# GBWandR1.net
KiCad netlist of a schematic drawn in EAGLE
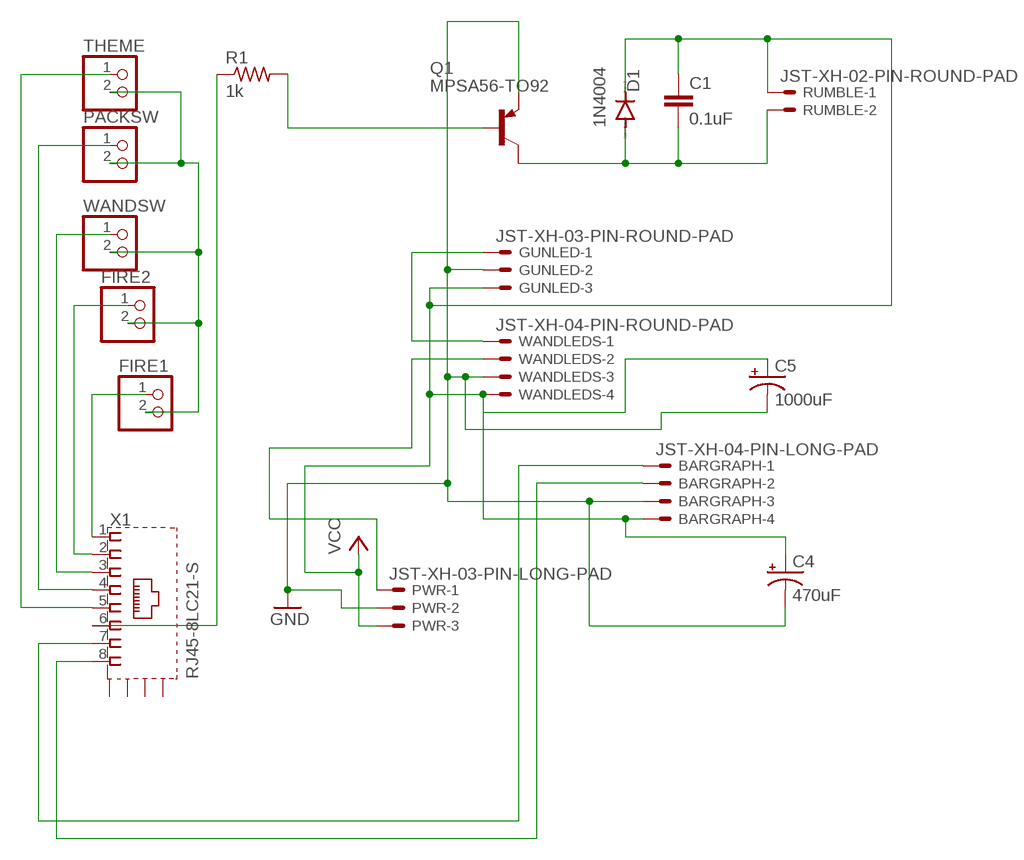
[diagram p0: schematic, sheet 1]

(export (version "E")
  (design (tool "Eeschema 10.0.6"))
  (components
    (comp (ref "BARGRAPH")
      (value "JST-XH-04-PIN-LONG-PAD")
      (footprint "eagle-import:JST-XH-04-PACKAGE-LONG-PAD")
      (libsource (lib "eagle-import") (part "JST-XH-04-PIN-LONG-PAD"))
    )
    (comp (ref "C1")
      (value "0.1uF")
      (footprint "eagle-import:C050-024X044")
      (libsource (lib "eagle-import") (part "C-EU050-024X044"))
    )
    (comp (ref "C4")
      (value "470uF")
      (footprint "eagle-import:E3,5-8")
      (libsource (lib "eagle-import") (part "CPOL-USE3.5-8"))
    )
    (comp (ref "C5")
      (value "1000uF")
      (footprint "eagle-import:E3,5-8")
      (libsource (lib "eagle-import") (part "CPOL-USE3.5-8"))
    )
    (comp (ref "D1")
      (value "1N4004")
      (footprint "eagle-import:DO41-10")
      (libsource (lib "eagle-import") (part "1N4004"))
    )
    (comp (ref "FIRE1")
      (value "PINHD-1X2")
      (footprint "eagle-import:1X02")
      (libsource (lib "eagle-import") (part "PINHD-1X2"))
    )
    (comp (ref "FIRE2")
      (value "PINHD-1X2")
      (footprint "eagle-import:1X02")
      (libsource (lib "eagle-import") (part "PINHD-1X2"))
    )
    (comp (ref "GUNLED")
      (value "JST-XH-03-PIN-ROUND-PAD")
      (footprint "eagle-import:JST-XH-03-PACKAGE-ROUND-PAD")
      (libsource (lib "eagle-import") (part "JST-XH-03-PIN-ROUND-PAD"))
    )
    (comp (ref "PACKSW")
      (value "PINHD-1X2")
      (footprint "eagle-import:1X02")
      (libsource (lib "eagle-import") (part "PINHD-1X2"))
    )
    (comp (ref "PWR")
      (value "JST-XH-03-PIN-LONG-PAD")
      (footprint "eagle-import:JST-XH-03-PACKAGE-LONG-PAD")
      (libsource (lib "eagle-import") (part "JST-XH-03-PIN-LONG-PAD"))
    )
    (comp (ref "Q1")
      (value "MPSA56-TO92")
      (footprint "eagle-import:TO92-CBE")
      (libsource (lib "eagle-import") (part "-?TO92MPSA56"))
    )
    (comp (ref "R1")
      (value "1k")
      (footprint "eagle-import:0207_9")
      (libsource (lib "eagle-import") (part "R-US_0207/9"))
    )
    (comp (ref "RUMBLE")
      (value "JST-XH-02-PIN-ROUND-PAD")
      (footprint "eagle-import:JST-XH-02-PACKAGE-ROUND-PAD")
      (libsource (lib "eagle-import") (part "JST-XH-02-PIN-ROUND-PAD"))
    )
    (comp (ref "THEME")
      (value "PINHD-1X2")
      (footprint "eagle-import:1X02")
      (libsource (lib "eagle-import") (part "PINHD-1X2"))
    )
    (comp (ref "WANDLEDS")
      (value "JST-XH-04-PIN-ROUND-PAD")
      (footprint "eagle-import:JST-XH-04-PACKAGE-ROUND-PAD")
      (libsource (lib "eagle-import") (part "JST-XH-04-PIN-ROUND-PAD"))
    )
    (comp (ref "WANDSW")
      (value "PINHD-1X2")
      (footprint "eagle-import:1X02")
      (libsource (lib "eagle-import") (part "PINHD-1X2"))
    )
    (comp (ref "X1")
      (value "RJ45-8LC21-S")
      (footprint "eagle-import:RJ45-SHIELD1")
      (libsource (lib "eagle-import") (part "RJ4521-S-8LC"))
    )
  )
  (nets
    (net (code "1") (name "GND") (class "Default")
      (node (ref "BARGRAPH") (pin "3") (pinfunction "S_3") (pintype "passive"))
      (node (ref "C4") (pin "-") (pinfunction "-_-") (pintype "passive"))
      (node (ref "C5") (pin "-") (pinfunction "-_-") (pintype "passive"))
      (node (ref "GUNLED") (pin "2") (pinfunction "S_2") (pintype "passive"))
      (node (ref "PWR") (pin "2") (pinfunction "S_2") (pintype "passive"))
      (node (ref "Q1") (pin "E") (pinfunction "E_E") (pintype "passive"))
      (node (ref "WANDLEDS") (pin "3") (pinfunction "S_3") (pintype "passive"))
    )
    (net (code "2") (name "Net-(BARGRAPHA-S)") (class "Default")
      (node (ref "BARGRAPH") (pin "1") (pinfunction "S_1") (pintype "passive"))
      (node (ref "X1") (pin "7") (pinfunction "7_7") (pintype "passive"))
    )
    (net (code "3") (name "Net-(BARGRAPHB-S)") (class "Default")
      (node (ref "BARGRAPH") (pin "2") (pinfunction "S_2") (pintype "passive"))
      (node (ref "X1") (pin "8") (pinfunction "8_8") (pintype "passive"))
    )
    (net (code "4") (name "Net-(FIRE1-Pad1)") (class "Default")
      (node (ref "FIRE1") (pin "1") (pinfunction "1_1") (pintype "passive"))
      (node (ref "X1") (pin "1") (pinfunction "1_1") (pintype "passive"))
    )
    (net (code "5") (name "Net-(FIRE1-Pad2)") (class "Default")
      (node (ref "FIRE1") (pin "2") (pinfunction "2_2") (pintype "passive"))
      (node (ref "FIRE2") (pin "2") (pinfunction "2_2") (pintype "passive"))
      (node (ref "PACKSW") (pin "2") (pinfunction "2_2") (pintype "passive"))
      (node (ref "THEME") (pin "2") (pinfunction "2_2") (pintype "passive"))
      (node (ref "WANDSW") (pin "2") (pinfunction "2_2") (pintype "passive"))
    )
    (net (code "6") (name "Net-(FIRE2-Pad1)") (class "Default")
      (node (ref "FIRE2") (pin "1") (pinfunction "1_1") (pintype "passive"))
      (node (ref "X1") (pin "2") (pinfunction "2_2") (pintype "passive"))
    )
    (net (code "7") (name "Net-(GUNLEDA-S)") (class "Default")
      (node (ref "GUNLED") (pin "1") (pinfunction "S_1") (pintype "passive"))
      (node (ref "WANDLEDS") (pin "1") (pinfunction "S_1") (pintype "passive"))
    )
    (net (code "8") (name "Net-(PACKSW-Pad1)") (class "Default")
      (node (ref "PACKSW") (pin "1") (pinfunction "1_1") (pintype "passive"))
      (node (ref "X1") (pin "4") (pinfunction "4_4") (pintype "passive"))
    )
    (net (code "9") (name "Net-(PWRA-S)") (class "Default")
      (node (ref "PWR") (pin "1") (pinfunction "S_1") (pintype "passive"))
      (node (ref "WANDLEDS") (pin "2") (pinfunction "S_2") (pintype "passive"))
    )
    (net (code "10") (name "Net-(Q1-PadB)") (class "Default")
      (node (ref "Q1") (pin "B") (pinfunction "B_B") (pintype "passive"))
      (node (ref "R1") (pin "2") (pinfunction "2_2") (pintype "passive"))
    )
    (net (code "11") (name "Net-(R1-Pad1)") (class "Default")
      (node (ref "R1") (pin "1") (pinfunction "1_1") (pintype "passive"))
      (node (ref "X1") (pin "6") (pinfunction "6_6") (pintype "passive"))
    )
    (net (code "12") (name "Net-(RUMBLEB-S)") (class "Default")
      (node (ref "C1") (pin "2") (pinfunction "2_2") (pintype "passive"))
      (node (ref "D1") (pin "A") (pinfunction "A_A") (pintype "passive"))
      (node (ref "Q1") (pin "C") (pinfunction "C_C") (pintype "passive"))
      (node (ref "RUMBLE") (pin "2") (pinfunction "S_2") (pintype "passive"))
    )
    (net (code "13") (name "Net-(THEME-Pad1)") (class "Default")
      (node (ref "THEME") (pin "1") (pinfunction "1_1") (pintype "passive"))
      (node (ref "X1") (pin "5") (pinfunction "5_5") (pintype "passive"))
    )
    (net (code "14") (name "Net-(WANDSW-Pad1)") (class "Default")
      (node (ref "WANDSW") (pin "1") (pinfunction "1_1") (pintype "passive"))
      (node (ref "X1") (pin "3") (pinfunction "3_3") (pintype "passive"))
    )
    (net (code "15") (name "VCC") (class "Default")
      (node (ref "BARGRAPH") (pin "4") (pinfunction "S_4") (pintype "passive"))
      (node (ref "C1") (pin "1") (pinfunction "1_1") (pintype "passive"))
      (node (ref "C4") (pin "+") (pinfunction "+_+") (pintype "passive"))
      (node (ref "C5") (pin "+") (pinfunction "+_+") (pintype "passive"))
      (node (ref "D1") (pin "C") (pinfunction "C_C") (pintype "passive"))
      (node (ref "GUNLED") (pin "3") (pinfunction "S_3") (pintype "passive"))
      (node (ref "PWR") (pin "3") (pinfunction "S_3") (pintype "passive"))
      (node (ref "RUMBLE") (pin "1") (pinfunction "S_1") (pintype "passive"))
      (node (ref "WANDLEDS") (pin "4") (pinfunction "S_4") (pintype "passive"))
    )
    (net (code "16") (name "unconnected-(X1-S-PadS1)") (class "Default")
      (node (ref "X1") (pin "S1") (pinfunction "S_S1") (pintype "passive"))
    )
    (net (code "17") (name "unconnected-(X1-S-PadS2)") (class "Default")
      (node (ref "X1") (pin "S2") (pinfunction "S_S2") (pintype "passive"))
    )
    (net (code "18") (name "unconnected-(X1-S-PadS3)") (class "Default")
      (node (ref "X1") (pin "S3") (pinfunction "S_S3") (pintype "passive"))
    )
    (net (code "19") (name "unconnected-(X1-S-PadS4)") (class "Default")
      (node (ref "X1") (pin "S4") (pinfunction "S_S4") (pintype "passive"))
    )
  )
)
